# source_eagle.net
KiCad netlist of a schematic drawn in EAGLE
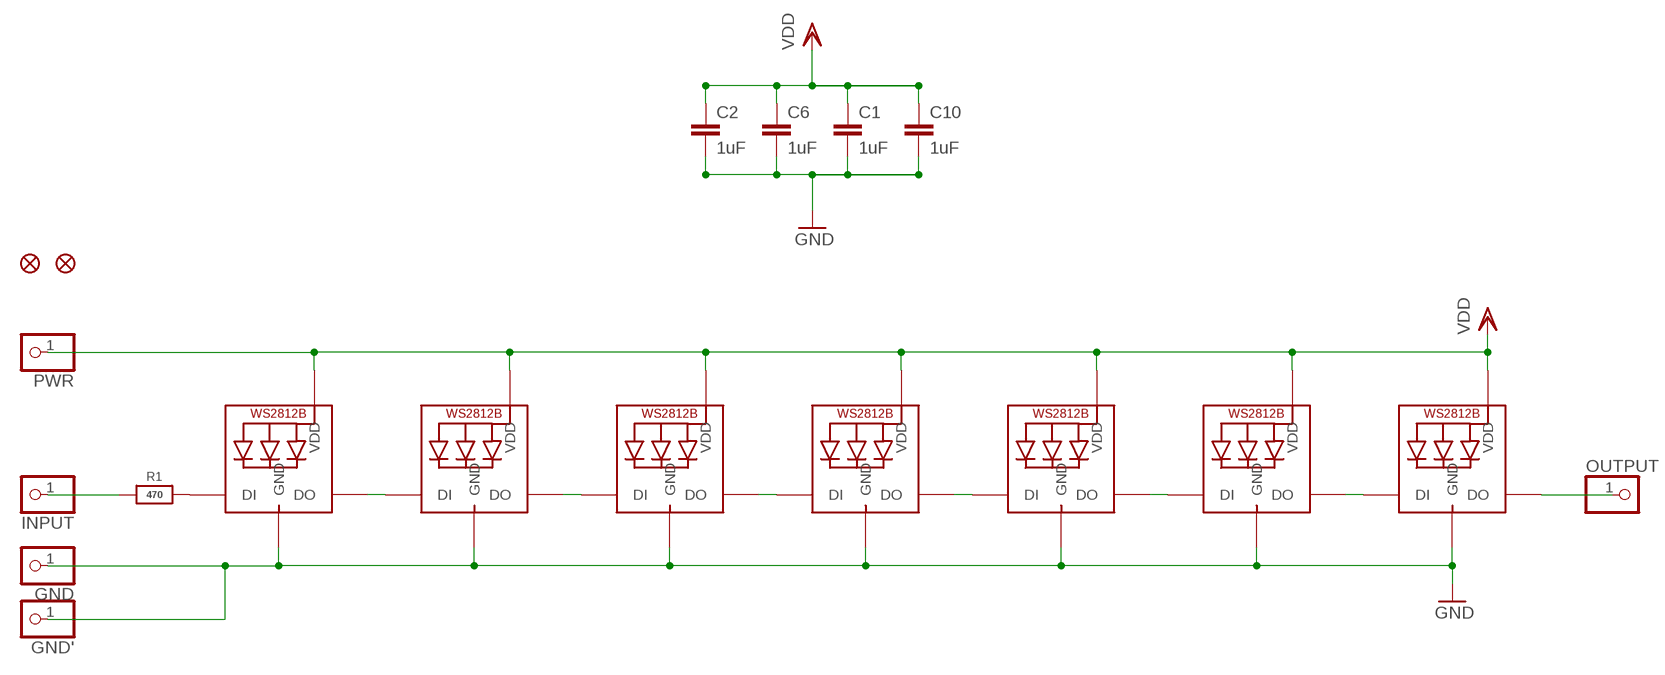
[diagram p0: schematic, sheet 1]

(export (version "E")
  (design (tool "Eeschema 10.0.6"))
  (components
    (comp (ref "C1")
      (value "1uF")
      (footprint "eagle-import:C0603")
      (libsource (lib "eagle-import") (part "C-EUC0603"))
    )
    (comp (ref "C2")
      (value "1uF")
      (footprint "eagle-import:C0603")
      (libsource (lib "eagle-import") (part "C-EUC0603"))
    )
    (comp (ref "C6")
      (value "1uF")
      (footprint "eagle-import:C0603")
      (libsource (lib "eagle-import") (part "C-EUC0603"))
    )
    (comp (ref "C10")
      (value "1uF")
      (footprint "eagle-import:C0603")
      (libsource (lib "eagle-import") (part "C-EUC0603"))
    )
    (comp (ref "FID1")
      (value "FIDUCIAL_1MM")
      (footprint "eagle-import:FIDUCIAL_1MM")
      (libsource (lib "eagle-import") (part "FIDUCIAL_1MM"))
    )
    (comp (ref "FID2")
      (value "FIDUCIAL_1MM")
      (footprint "eagle-import:FIDUCIAL_1MM")
      (libsource (lib "eagle-import") (part "FIDUCIAL_1MM"))
    )
    (comp (ref "GND")
      (value "PINHD-1X1CB")
      (footprint "eagle-import:1X01-CLEANBIG")
      (libsource (lib "eagle-import") (part "PINHD-1X1CB"))
    )
    (comp (ref "GND'")
      (value "PINHD-1X1CB")
      (footprint "eagle-import:1X01-CLEANBIG")
      (libsource (lib "eagle-import") (part "PINHD-1X1CB"))
    )
    (comp (ref "INPUT")
      (value "PINHD-1X1CB")
      (footprint "eagle-import:1X01-CLEANBIG")
      (libsource (lib "eagle-import") (part "PINHD-1X1CB"))
    )
    (comp (ref "LED1")
      (value "WS2812B_5050N")
      (footprint "eagle-import:WS2812B-NARROW")
      (libsource (lib "eagle-import") (part "WS2812B_5050N"))
    )
    (comp (ref "LED2")
      (value "WS2812B_5050N")
      (footprint "eagle-import:WS2812B-NARROW")
      (libsource (lib "eagle-import") (part "WS2812B_5050N"))
    )
    (comp (ref "LED3")
      (value "WS2812B_5050N")
      (footprint "eagle-import:WS2812B-NARROW")
      (libsource (lib "eagle-import") (part "WS2812B_5050N"))
    )
    (comp (ref "LED4")
      (value "WS2812B_5050N")
      (footprint "eagle-import:WS2812B-NARROW")
      (libsource (lib "eagle-import") (part "WS2812B_5050N"))
    )
    (comp (ref "LED5")
      (value "WS2812B_5050N")
      (footprint "eagle-import:WS2812B-NARROW")
      (libsource (lib "eagle-import") (part "WS2812B_5050N"))
    )
    (comp (ref "LED6")
      (value "WS2812B_5050N")
      (footprint "eagle-import:WS2812B-NARROW")
      (libsource (lib "eagle-import") (part "WS2812B_5050N"))
    )
    (comp (ref "LED7")
      (value "WS2812B_5050N")
      (footprint "eagle-import:WS2812B-NARROW")
      (libsource (lib "eagle-import") (part "WS2812B_5050N"))
    )
    (comp (ref "OUTPUT")
      (value "PINHD-1X1CB")
      (footprint "eagle-import:1X01-CLEANBIG")
      (libsource (lib "eagle-import") (part "PINHD-1X1CB"))
    )
    (comp (ref "PWR")
      (value "PINHD-1X1CB")
      (footprint "eagle-import:1X01-CLEANBIG")
      (libsource (lib "eagle-import") (part "PINHD-1X1CB"))
    )
    (comp (ref "R1")
      (value "470")
      (footprint "eagle-import:0603-NO")
      (libsource (lib "eagle-import") (part "RESISTOR_0603_NOOUT"))
    )
  )
  (nets
    (net (code "1") (name "GND") (class "Default")
      (node (ref "C1") (pin "2") (pinfunction "2_2") (pintype "passive"))
      (node (ref "C10") (pin "2") (pinfunction "2_2") (pintype "passive"))
      (node (ref "C2") (pin "2") (pinfunction "2_2") (pintype "passive"))
      (node (ref "C6") (pin "2") (pinfunction "2_2") (pintype "passive"))
      (node (ref "GND") (pin "1") (pinfunction "1_1") (pintype "passive"))
      (node (ref "GND'") (pin "1") (pinfunction "1_1") (pintype "passive"))
      (node (ref "LED1") (pin "3-GND") (pinfunction "GND_3-GND") (pintype "power_in"))
      (node (ref "LED2") (pin "3-GND") (pinfunction "GND_3-GND") (pintype "power_in"))
      (node (ref "LED3") (pin "3-GND") (pinfunction "GND_3-GND") (pintype "power_in"))
      (node (ref "LED4") (pin "3-GND") (pinfunction "GND_3-GND") (pintype "power_in"))
      (node (ref "LED5") (pin "3-GND") (pinfunction "GND_3-GND") (pintype "power_in"))
      (node (ref "LED6") (pin "3-GND") (pinfunction "GND_3-GND") (pintype "power_in"))
      (node (ref "LED7") (pin "3-GND") (pinfunction "GND_3-GND") (pintype "power_in"))
    )
    (net (code "2") (name "Net-(INPUT-Pad1)") (class "Default")
      (node (ref "INPUT") (pin "1") (pinfunction "1_1") (pintype "passive"))
      (node (ref "R1") (pin "1") (pinfunction "1_1") (pintype "passive"))
    )
    (net (code "3") (name "Net-(LED1-DI)") (class "Default")
      (node (ref "LED1") (pin "4-DIN") (pinfunction "DI_4-DIN") (pintype "input"))
      (node (ref "R1") (pin "2") (pinfunction "2_2") (pintype "passive"))
    )
    (net (code "4") (name "Net-(LED1-DO)") (class "Default")
      (node (ref "LED1") (pin "2-DOUT") (pinfunction "DO_2-DOUT") (pintype "output"))
      (node (ref "LED2") (pin "4-DIN") (pinfunction "DI_4-DIN") (pintype "input"))
    )
    (net (code "5") (name "Net-(LED2-DO)") (class "Default")
      (node (ref "LED2") (pin "2-DOUT") (pinfunction "DO_2-DOUT") (pintype "output"))
      (node (ref "LED3") (pin "4-DIN") (pinfunction "DI_4-DIN") (pintype "input"))
    )
    (net (code "6") (name "Net-(LED3-DO)") (class "Default")
      (node (ref "LED3") (pin "2-DOUT") (pinfunction "DO_2-DOUT") (pintype "output"))
      (node (ref "LED4") (pin "4-DIN") (pinfunction "DI_4-DIN") (pintype "input"))
    )
    (net (code "7") (name "Net-(LED4-DO)") (class "Default")
      (node (ref "LED4") (pin "2-DOUT") (pinfunction "DO_2-DOUT") (pintype "output"))
      (node (ref "LED5") (pin "4-DIN") (pinfunction "DI_4-DIN") (pintype "input"))
    )
    (net (code "8") (name "Net-(LED5-DO)") (class "Default")
      (node (ref "LED5") (pin "2-DOUT") (pinfunction "DO_2-DOUT") (pintype "output"))
      (node (ref "LED6") (pin "4-DIN") (pinfunction "DI_4-DIN") (pintype "input"))
    )
    (net (code "9") (name "Net-(LED6-DO)") (class "Default")
      (node (ref "LED6") (pin "2-DOUT") (pinfunction "DO_2-DOUT") (pintype "output"))
      (node (ref "LED7") (pin "4-DIN") (pinfunction "DI_4-DIN") (pintype "input"))
    )
    (net (code "10") (name "Net-(LED7-DO)") (class "Default")
      (node (ref "LED7") (pin "2-DOUT") (pinfunction "DO_2-DOUT") (pintype "output"))
      (node (ref "OUTPUT") (pin "1") (pinfunction "1_1") (pintype "passive"))
    )
    (net (code "11") (name "VDD") (class "Default")
      (node (ref "C1") (pin "1") (pinfunction "1_1") (pintype "passive"))
      (node (ref "C10") (pin "1") (pinfunction "1_1") (pintype "passive"))
      (node (ref "C2") (pin "1") (pinfunction "1_1") (pintype "passive"))
      (node (ref "C6") (pin "1") (pinfunction "1_1") (pintype "passive"))
      (node (ref "LED1") (pin "1-VDD") (pinfunction "VDD_1-VDD") (pintype "power_in"))
      (node (ref "LED2") (pin "1-VDD") (pinfunction "VDD_1-VDD") (pintype "power_in"))
      (node (ref "LED3") (pin "1-VDD") (pinfunction "VDD_1-VDD") (pintype "power_in"))
      (node (ref "LED4") (pin "1-VDD") (pinfunction "VDD_1-VDD") (pintype "power_in"))
      (node (ref "LED5") (pin "1-VDD") (pinfunction "VDD_1-VDD") (pintype "power_in"))
      (node (ref "LED6") (pin "1-VDD") (pinfunction "VDD_1-VDD") (pintype "power_in"))
      (node (ref "LED7") (pin "1-VDD") (pinfunction "VDD_1-VDD") (pintype "power_in"))
      (node (ref "PWR") (pin "1") (pinfunction "1_1") (pintype "passive"))
    )
  )
)
